# 4_shkb_downstream_power.net
KiCad netlist of a schematic drawn in Altium Designer
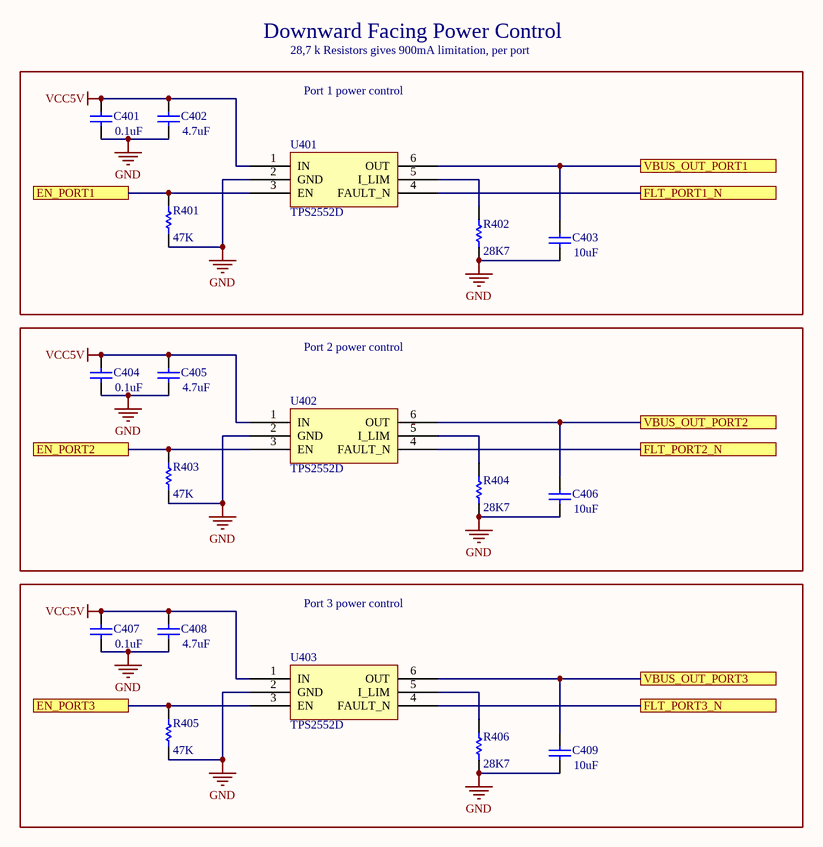
[diagram p0: 4_shkb_downstream_power.SchDoc]

(export (version "E")
  (design (tool "Eeschema 10.0.6"))
  (components
    (comp (ref "C401")
      (value "0.1uF")
      (footprint "C0603[1608]")
      (description "Capacitor")
      (fields (field (name "MFG") "KEMET") (field (name "LCSC PART #") "C14663"))
      (libsource (lib "Miscellaneous Devices") (part "Cap"))
    )
    (comp (ref "C402")
      (value "4.7uF")
      (footprint "C1206[3216]")
      (description "Capacitor")
      (fields (field (name "MFG") "KEMET") (field (name "LCSC PART #") "C29823"))
      (libsource (lib "Miscellaneous Devices") (part "Cap"))
    )
    (comp (ref "C403")
      (value "10uF")
      (footprint "C1206[3216]")
      (description "Capacitor")
      (fields (field (name "MFG") "KEMET") (field (name "LCSC PART #") "C13585"))
      (libsource (lib "Miscellaneous Devices") (part "Cap"))
    )
    (comp (ref "C404")
      (value "0.1uF")
      (footprint "C0603[1608]")
      (description "Capacitor")
      (fields (field (name "MFG") "KEMET") (field (name "LCSC PART #") "C14663"))
      (libsource (lib "Miscellaneous Devices") (part "Cap"))
    )
    (comp (ref "C405")
      (value "4.7uF")
      (footprint "C1206[3216]")
      (description "Capacitor")
      (fields (field (name "MFG") "KEMET") (field (name "LCSC PART #") "C29823"))
      (libsource (lib "Miscellaneous Devices") (part "Cap"))
    )
    (comp (ref "C406")
      (value "10uF")
      (footprint "C1206[3216]")
      (description "Capacitor")
      (fields (field (name "MFG") "KEMET") (field (name "LCSC PART #") "C13585"))
      (libsource (lib "Miscellaneous Devices") (part "Cap"))
    )
    (comp (ref "C407")
      (value "0.1uF")
      (footprint "C0603[1608]")
      (description "Capacitor")
      (fields (field (name "MFG") "KEMET") (field (name "LCSC PART #") "C14663"))
      (libsource (lib "Miscellaneous Devices") (part "Cap"))
    )
    (comp (ref "C408")
      (value "4.7uF")
      (footprint "C1206[3216]")
      (description "Capacitor")
      (fields (field (name "MFG") "KEMET") (field (name "LCSC PART #") "C29823"))
      (libsource (lib "Miscellaneous Devices") (part "Cap"))
    )
    (comp (ref "C409")
      (value "10uF")
      (footprint "C1206[3216]")
      (description "Capacitor")
      (fields (field (name "MFG") "KEMET") (field (name "LCSC PART #") "C13585"))
      (libsource (lib "Miscellaneous Devices") (part "Cap"))
    )
    (comp (ref "R401")
      (value "47K")
      (footprint "R0603[1608]")
      (description "Resistor")
      (fields (field (name "MFG") "Vishay Dale") (field (name "LCSC PART #") "C25819"))
      (libsource (lib "Miscellaneous Devices") (part "Res1"))
    )
    (comp (ref "R402")
      (value "28K7")
      (footprint "R0603[1608]")
      (description "Resistor")
      (fields (field (name "MFG") "Vishay Dale") (field (name "LCSC PART #") "C22928"))
      (libsource (lib "Miscellaneous Devices") (part "Res1"))
    )
    (comp (ref "R403")
      (value "47K")
      (footprint "R0603[1608]")
      (description "Resistor")
      (fields (field (name "MFG") "Vishay Dale") (field (name "LCSC PART #") "C25819"))
      (libsource (lib "Miscellaneous Devices") (part "Res1"))
    )
    (comp (ref "R404")
      (value "28K7")
      (footprint "R0603[1608]")
      (description "Resistor")
      (fields (field (name "MFG") "Vishay Dale") (field (name "LCSC PART #") "C22928"))
      (libsource (lib "Miscellaneous Devices") (part "Res1"))
    )
    (comp (ref "R405")
      (value "47K")
      (footprint "R0603[1608]")
      (description "Resistor")
      (fields (field (name "MFG") "Vishay Dale") (field (name "LCSC PART #") "C25819"))
      (libsource (lib "Miscellaneous Devices") (part "Res1"))
    )
    (comp (ref "R406")
      (value "28K7")
      (footprint "R0603[1608]")
      (description "Resistor")
      (fields (field (name "MFG") "Vishay Dale") (field (name "LCSC PART #") "C22928"))
      (libsource (lib "Miscellaneous Devices") (part "Res1"))
    )
    (comp (ref "U401")
      (value "TPS2552D")
      (footprint "SOT-23-6")
      (fields (field (name "LCSC PART #") "C140331") (field (name "MRF.PART") "TPS2552DBVR-1"))
      (libsource (lib "lib") (part "TPS2552D"))
    )
    (comp (ref "U402")
      (value "TPS2552D")
      (footprint "SOT-23-6")
      (fields (field (name "LCSC PART #") "C140331") (field (name "MRF.PART") "TPS2552DBVR-1"))
      (libsource (lib "lib") (part "TPS2552D"))
    )
    (comp (ref "U403")
      (value "TPS2552D")
      (footprint "SOT-23-6")
      (fields (field (name "LCSC PART #") "C140331") (field (name "MRF.PART") "TPS2552DBVR-1"))
      (libsource (lib "lib") (part "TPS2552D"))
    )
  )
  (nets
    (net (code "1") (name "/EN_PORT1") (class "Default")
      (node (ref "R401") (pin "1") (pinfunction "1_1") (pintype "passive"))
      (node (ref "U401") (pin "3") (pinfunction "EN_3") (pintype "passive"))
    )
    (net (code "2") (name "/EN_PORT2") (class "Default")
      (node (ref "R403") (pin "1") (pinfunction "1_1") (pintype "passive"))
      (node (ref "U402") (pin "3") (pinfunction "EN_3") (pintype "passive"))
    )
    (net (code "3") (name "/EN_PORT3") (class "Default")
      (node (ref "R405") (pin "1") (pinfunction "1_1") (pintype "passive"))
      (node (ref "U403") (pin "3") (pinfunction "EN_3") (pintype "passive"))
    )
    (net (code "4") (name "/FLT_PORT1_N") (class "Default")
      (node (ref "U401") (pin "4") (pinfunction "FAULT_N_4") (pintype "passive"))
    )
    (net (code "5") (name "/FLT_PORT2_N") (class "Default")
      (node (ref "U402") (pin "4") (pinfunction "FAULT_N_4") (pintype "passive"))
    )
    (net (code "6") (name "/FLT_PORT3_N") (class "Default")
      (node (ref "U403") (pin "4") (pinfunction "FAULT_N_4") (pintype "passive"))
    )
    (net (code "7") (name "/VBUS_OUT_PORT1") (class "Default")
      (node (ref "C403") (pin "2") (pinfunction "2_2") (pintype "passive"))
      (node (ref "U401") (pin "6") (pinfunction "OUT_6") (pintype "passive"))
    )
    (net (code "8") (name "/VBUS_OUT_PORT2") (class "Default")
      (node (ref "C406") (pin "2") (pinfunction "2_2") (pintype "passive"))
      (node (ref "U402") (pin "6") (pinfunction "OUT_6") (pintype "passive"))
    )
    (net (code "9") (name "/VBUS_OUT_PORT3") (class "Default")
      (node (ref "C409") (pin "2") (pinfunction "2_2") (pintype "passive"))
      (node (ref "U403") (pin "6") (pinfunction "OUT_6") (pintype "passive"))
    )
    (net (code "10") (name "GND") (class "Default")
      (node (ref "C401") (pin "1") (pinfunction "1_1") (pintype "passive"))
      (node (ref "C402") (pin "1") (pinfunction "1_1") (pintype "passive"))
      (node (ref "C403") (pin "1") (pinfunction "1_1") (pintype "passive"))
      (node (ref "C404") (pin "1") (pinfunction "1_1") (pintype "passive"))
      (node (ref "C405") (pin "1") (pinfunction "1_1") (pintype "passive"))
      (node (ref "C406") (pin "1") (pinfunction "1_1") (pintype "passive"))
      (node (ref "C407") (pin "1") (pinfunction "1_1") (pintype "passive"))
      (node (ref "C408") (pin "1") (pinfunction "1_1") (pintype "passive"))
      (node (ref "C409") (pin "1") (pinfunction "1_1") (pintype "passive"))
      (node (ref "R401") (pin "2") (pinfunction "2_2") (pintype "passive"))
      (node (ref "R402") (pin "2") (pinfunction "2_2") (pintype "passive"))
      (node (ref "R403") (pin "2") (pinfunction "2_2") (pintype "passive"))
      (node (ref "R404") (pin "2") (pinfunction "2_2") (pintype "passive"))
      (node (ref "R405") (pin "2") (pinfunction "2_2") (pintype "passive"))
      (node (ref "R406") (pin "2") (pinfunction "2_2") (pintype "passive"))
      (node (ref "U401") (pin "2") (pinfunction "GND_2") (pintype "passive"))
      (node (ref "U402") (pin "2") (pinfunction "GND_2") (pintype "passive"))
      (node (ref "U403") (pin "2") (pinfunction "GND_2") (pintype "passive"))
    )
    (net (code "11") (name "Net-(U401-I_LIM)") (class "Default")
      (node (ref "R402") (pin "1") (pinfunction "1_1") (pintype "passive"))
      (node (ref "U401") (pin "5") (pinfunction "I_LIM_5") (pintype "passive"))
    )
    (net (code "12") (name "Net-(U402-I_LIM)") (class "Default")
      (node (ref "R404") (pin "1") (pinfunction "1_1") (pintype "passive"))
      (node (ref "U402") (pin "5") (pinfunction "I_LIM_5") (pintype "passive"))
    )
    (net (code "13") (name "Net-(U403-I_LIM)") (class "Default")
      (node (ref "R406") (pin "1") (pinfunction "1_1") (pintype "passive"))
      (node (ref "U403") (pin "5") (pinfunction "I_LIM_5") (pintype "passive"))
    )
    (net (code "14") (name "VCC5V") (class "Default")
      (node (ref "C401") (pin "2") (pinfunction "2_2") (pintype "passive"))
      (node (ref "C402") (pin "2") (pinfunction "2_2") (pintype "passive"))
      (node (ref "C404") (pin "2") (pinfunction "2_2") (pintype "passive"))
      (node (ref "C405") (pin "2") (pinfunction "2_2") (pintype "passive"))
      (node (ref "C407") (pin "2") (pinfunction "2_2") (pintype "passive"))
      (node (ref "C408") (pin "2") (pinfunction "2_2") (pintype "passive"))
      (node (ref "U401") (pin "1") (pinfunction "IN_1") (pintype "passive"))
      (node (ref "U402") (pin "1") (pinfunction "IN_1") (pintype "passive"))
      (node (ref "U403") (pin "1") (pinfunction "IN_1") (pintype "passive"))
    )
  )
)
